# OneSideOfBoard.net
KiCad netlist of a schematic drawn in Altium Designer
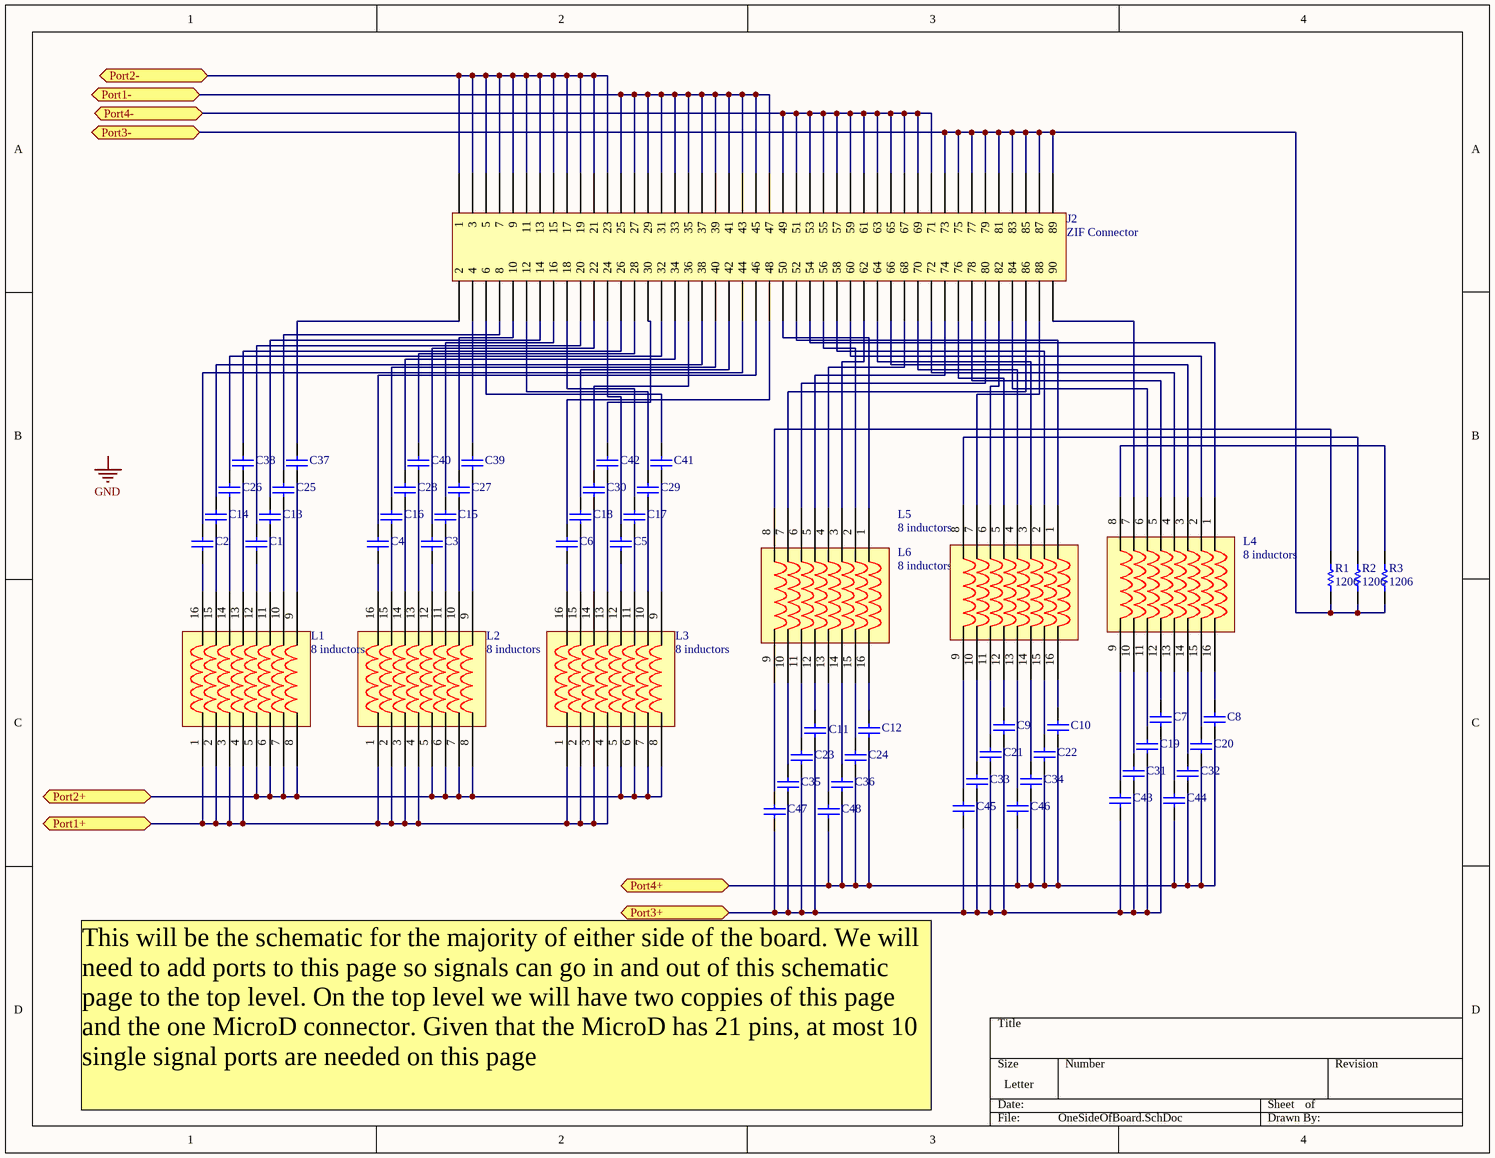
[diagram p0: OneSideOfBoard.SchDoc]

(export (version "E")
  (design (tool "Eeschema 10.0.6"))
  (components
    (comp (ref "C1")
      (value "47nF")
      (footprint "CC3216-1206")
      (description "Capacitor (Semiconductor SIM Model)")
      (fields (field (name "PUBLISHER") "Altium Limited"))
      (libsource (lib "altium-import") (part "root_1_Cap Semi_1_"))
    )
    (comp (ref "C2")
      (value "47nF")
      (footprint "CC3216-1206")
      (description "Capacitor (Semiconductor SIM Model)")
      (fields (field (name "PUBLISHER") "Altium Limited"))
      (libsource (lib "altium-import") (part "root_1_Cap Semi_1_"))
    )
    (comp (ref "C3")
      (value "47nF")
      (footprint "CC3216-1206")
      (description "Capacitor (Semiconductor SIM Model)")
      (fields (field (name "PUBLISHER") "Altium Limited"))
      (libsource (lib "altium-import") (part "root_1_Cap Semi_1_"))
    )
    (comp (ref "C4")
      (value "47nF")
      (footprint "CC3216-1206")
      (description "Capacitor (Semiconductor SIM Model)")
      (fields (field (name "PUBLISHER") "Altium Limited"))
      (libsource (lib "altium-import") (part "root_1_Cap Semi_1_"))
    )
    (comp (ref "C5")
      (value "47nF")
      (footprint "CC3216-1206")
      (description "Capacitor (Semiconductor SIM Model)")
      (fields (field (name "PUBLISHER") "Altium Limited"))
      (libsource (lib "altium-import") (part "root_1_Cap Semi_1_"))
    )
    (comp (ref "C6")
      (value "47nF")
      (footprint "CC3216-1206")
      (description "Capacitor (Semiconductor SIM Model)")
      (fields (field (name "PUBLISHER") "Altium Limited"))
      (libsource (lib "altium-import") (part "root_1_Cap Semi_1_"))
    )
    (comp (ref "C7")
      (value "47nF")
      (footprint "CC3216-1206")
      (description "Capacitor (Semiconductor SIM Model)")
      (fields (field (name "PUBLISHER") "Altium Limited"))
      (libsource (lib "altium-import") (part "root_3_Cap Semi_1_"))
    )
    (comp (ref "C8")
      (value "47nF")
      (footprint "CC3216-1206")
      (description "Capacitor (Semiconductor SIM Model)")
      (fields (field (name "PUBLISHER") "Altium Limited"))
      (libsource (lib "altium-import") (part "root_3_Cap Semi_1_"))
    )
    (comp (ref "C9")
      (value "47nF")
      (footprint "CC3216-1206")
      (description "Capacitor (Semiconductor SIM Model)")
      (fields (field (name "PUBLISHER") "Altium Limited"))
      (libsource (lib "altium-import") (part "root_3_Cap Semi_1_"))
    )
    (comp (ref "C10")
      (value "47nF")
      (footprint "CC3216-1206")
      (description "Capacitor (Semiconductor SIM Model)")
      (fields (field (name "PUBLISHER") "Altium Limited"))
      (libsource (lib "altium-import") (part "root_3_Cap Semi_1_"))
    )
    (comp (ref "C11")
      (value "47nF")
      (footprint "CC3216-1206")
      (description "Capacitor (Semiconductor SIM Model)")
      (fields (field (name "PUBLISHER") "Altium Limited"))
      (libsource (lib "altium-import") (part "root_3_Cap Semi_1_"))
    )
    (comp (ref "C12")
      (value "47nF")
      (footprint "CC3216-1206")
      (description "Capacitor (Semiconductor SIM Model)")
      (fields (field (name "PUBLISHER") "Altium Limited"))
      (libsource (lib "altium-import") (part "root_3_Cap Semi_1_"))
    )
    (comp (ref "C13")
      (value "47nF")
      (footprint "CC3216-1206")
      (description "Capacitor (Semiconductor SIM Model)")
      (fields (field (name "PUBLISHER") "Altium Limited"))
      (libsource (lib "altium-import") (part "root_1_Cap Semi_1_"))
    )
    (comp (ref "C14")
      (value "47nF")
      (footprint "CC3216-1206")
      (description "Capacitor (Semiconductor SIM Model)")
      (fields (field (name "PUBLISHER") "Altium Limited"))
      (libsource (lib "altium-import") (part "root_1_Cap Semi_1_"))
    )
    (comp (ref "C15")
      (value "47nF")
      (footprint "CC3216-1206")
      (description "Capacitor (Semiconductor SIM Model)")
      (fields (field (name "PUBLISHER") "Altium Limited"))
      (libsource (lib "altium-import") (part "root_1_Cap Semi_1_"))
    )
    (comp (ref "C16")
      (value "47nF")
      (footprint "CC3216-1206")
      (description "Capacitor (Semiconductor SIM Model)")
      (fields (field (name "PUBLISHER") "Altium Limited"))
      (libsource (lib "altium-import") (part "root_1_Cap Semi_1_"))
    )
    (comp (ref "C17")
      (value "47nF")
      (footprint "CC3216-1206")
      (description "Capacitor (Semiconductor SIM Model)")
      (fields (field (name "PUBLISHER") "Altium Limited"))
      (libsource (lib "altium-import") (part "root_1_Cap Semi_1_"))
    )
    (comp (ref "C18")
      (value "47nF")
      (footprint "CC3216-1206")
      (description "Capacitor (Semiconductor SIM Model)")
      (fields (field (name "PUBLISHER") "Altium Limited"))
      (libsource (lib "altium-import") (part "root_1_Cap Semi_1_"))
    )
    (comp (ref "C19")
      (value "47nF")
      (footprint "CC3216-1206")
      (description "Capacitor (Semiconductor SIM Model)")
      (fields (field (name "PUBLISHER") "Altium Limited"))
      (libsource (lib "altium-import") (part "root_3_Cap Semi_1_"))
    )
    (comp (ref "C20")
      (value "47nF")
      (footprint "CC3216-1206")
      (description "Capacitor (Semiconductor SIM Model)")
      (fields (field (name "PUBLISHER") "Altium Limited"))
      (libsource (lib "altium-import") (part "root_3_Cap Semi_1_"))
    )
    (comp (ref "C21")
      (value "47nF")
      (footprint "CC3216-1206")
      (description "Capacitor (Semiconductor SIM Model)")
      (fields (field (name "PUBLISHER") "Altium Limited"))
      (libsource (lib "altium-import") (part "root_3_Cap Semi_1_"))
    )
    (comp (ref "C22")
      (value "47nF")
      (footprint "CC3216-1206")
      (description "Capacitor (Semiconductor SIM Model)")
      (fields (field (name "PUBLISHER") "Altium Limited"))
      (libsource (lib "altium-import") (part "root_3_Cap Semi_1_"))
    )
    (comp (ref "C23")
      (value "47nF")
      (footprint "CC3216-1206")
      (description "Capacitor (Semiconductor SIM Model)")
      (fields (field (name "PUBLISHER") "Altium Limited"))
      (libsource (lib "altium-import") (part "root_3_Cap Semi_1_"))
    )
    (comp (ref "C24")
      (value "47nF")
      (footprint "CC3216-1206")
      (description "Capacitor (Semiconductor SIM Model)")
      (fields (field (name "PUBLISHER") "Altium Limited"))
      (libsource (lib "altium-import") (part "root_3_Cap Semi_1_"))
    )
    (comp (ref "C25")
      (value "47nF")
      (footprint "CC3216-1206")
      (description "Capacitor (Semiconductor SIM Model)")
      (fields (field (name "PUBLISHER") "Altium Limited"))
      (libsource (lib "altium-import") (part "root_1_Cap Semi_1_"))
    )
    (comp (ref "C26")
      (value "47nF")
      (footprint "CC3216-1206")
      (description "Capacitor (Semiconductor SIM Model)")
      (fields (field (name "PUBLISHER") "Altium Limited"))
      (libsource (lib "altium-import") (part "root_1_Cap Semi_1_"))
    )
    (comp (ref "C27")
      (value "47nF")
      (footprint "CC3216-1206")
      (description "Capacitor (Semiconductor SIM Model)")
      (fields (field (name "PUBLISHER") "Altium Limited"))
      (libsource (lib "altium-import") (part "root_1_Cap Semi_1_"))
    )
    (comp (ref "C28")
      (value "47nF")
      (footprint "CC3216-1206")
      (description "Capacitor (Semiconductor SIM Model)")
      (fields (field (name "PUBLISHER") "Altium Limited"))
      (libsource (lib "altium-import") (part "root_1_Cap Semi_1_"))
    )
    (comp (ref "C29")
      (value "47nF")
      (footprint "CC3216-1206")
      (description "Capacitor (Semiconductor SIM Model)")
      (fields (field (name "PUBLISHER") "Altium Limited"))
      (libsource (lib "altium-import") (part "root_1_Cap Semi_1_"))
    )
    (comp (ref "C30")
      (value "47nF")
      (footprint "CC3216-1206")
      (description "Capacitor (Semiconductor SIM Model)")
      (fields (field (name "PUBLISHER") "Altium Limited"))
      (libsource (lib "altium-import") (part "root_1_Cap Semi_1_"))
    )
    (comp (ref "C31")
      (value "47nF")
      (footprint "CC3216-1206")
      (description "Capacitor (Semiconductor SIM Model)")
      (fields (field (name "PUBLISHER") "Altium Limited"))
      (libsource (lib "altium-import") (part "root_3_Cap Semi_1_"))
    )
    (comp (ref "C32")
      (value "47nF")
      (footprint "CC3216-1206")
      (description "Capacitor (Semiconductor SIM Model)")
      (fields (field (name "PUBLISHER") "Altium Limited"))
      (libsource (lib "altium-import") (part "root_3_Cap Semi_1_"))
    )
    (comp (ref "C33")
      (value "47nF")
      (footprint "CC3216-1206")
      (description "Capacitor (Semiconductor SIM Model)")
      (fields (field (name "PUBLISHER") "Altium Limited"))
      (libsource (lib "altium-import") (part "root_3_Cap Semi_1_"))
    )
    (comp (ref "C34")
      (value "47nF")
      (footprint "CC3216-1206")
      (description "Capacitor (Semiconductor SIM Model)")
      (fields (field (name "PUBLISHER") "Altium Limited"))
      (libsource (lib "altium-import") (part "root_3_Cap Semi_1_"))
    )
    (comp (ref "C35")
      (value "47nF")
      (footprint "CC3216-1206")
      (description "Capacitor (Semiconductor SIM Model)")
      (fields (field (name "PUBLISHER") "Altium Limited"))
      (libsource (lib "altium-import") (part "root_3_Cap Semi_1_"))
    )
    (comp (ref "C36")
      (value "47nF")
      (footprint "CC3216-1206")
      (description "Capacitor (Semiconductor SIM Model)")
      (fields (field (name "PUBLISHER") "Altium Limited"))
      (libsource (lib "altium-import") (part "root_3_Cap Semi_1_"))
    )
    (comp (ref "C37")
      (value "47nF")
      (footprint "CC3216-1206")
      (description "Capacitor (Semiconductor SIM Model)")
      (fields (field (name "PUBLISHER") "Altium Limited"))
      (libsource (lib "altium-import") (part "root_1_Cap Semi_1_"))
    )
    (comp (ref "C38")
      (value "47nF")
      (footprint "CC3216-1206")
      (description "Capacitor (Semiconductor SIM Model)")
      (fields (field (name "PUBLISHER") "Altium Limited"))
      (libsource (lib "altium-import") (part "root_1_Cap Semi_1_"))
    )
    (comp (ref "C39")
      (value "47nF")
      (footprint "CC3216-1206")
      (description "Capacitor (Semiconductor SIM Model)")
      (fields (field (name "PUBLISHER") "Altium Limited"))
      (libsource (lib "altium-import") (part "root_1_Cap Semi_1_"))
    )
    (comp (ref "C40")
      (value "47nF")
      (footprint "CC3216-1206")
      (description "Capacitor (Semiconductor SIM Model)")
      (fields (field (name "PUBLISHER") "Altium Limited"))
      (libsource (lib "altium-import") (part "root_1_Cap Semi_1_"))
    )
    (comp (ref "C41")
      (value "47nF")
      (footprint "CC3216-1206")
      (description "Capacitor (Semiconductor SIM Model)")
      (fields (field (name "PUBLISHER") "Altium Limited"))
      (libsource (lib "altium-import") (part "root_1_Cap Semi_1_"))
    )
    (comp (ref "C42")
      (value "47nF")
      (footprint "CC3216-1206")
      (description "Capacitor (Semiconductor SIM Model)")
      (fields (field (name "PUBLISHER") "Altium Limited"))
      (libsource (lib "altium-import") (part "root_1_Cap Semi_1_"))
    )
    (comp (ref "C43")
      (value "47nF")
      (footprint "CC3216-1206")
      (description "Capacitor (Semiconductor SIM Model)")
      (fields (field (name "PUBLISHER") "Altium Limited"))
      (libsource (lib "altium-import") (part "root_3_Cap Semi_1_"))
    )
    (comp (ref "C44")
      (value "47nF")
      (footprint "CC3216-1206")
      (description "Capacitor (Semiconductor SIM Model)")
      (fields (field (name "PUBLISHER") "Altium Limited"))
      (libsource (lib "altium-import") (part "root_3_Cap Semi_1_"))
    )
    (comp (ref "C45")
      (value "47nF")
      (footprint "CC3216-1206")
      (description "Capacitor (Semiconductor SIM Model)")
      (fields (field (name "PUBLISHER") "Altium Limited"))
      (libsource (lib "altium-import") (part "root_3_Cap Semi_1_"))
    )
    (comp (ref "C46")
      (value "47nF")
      (footprint "CC3216-1206")
      (description "Capacitor (Semiconductor SIM Model)")
      (fields (field (name "PUBLISHER") "Altium Limited"))
      (libsource (lib "altium-import") (part "root_3_Cap Semi_1_"))
    )
    (comp (ref "C47")
      (value "47nF")
      (footprint "CC3216-1206")
      (description "Capacitor (Semiconductor SIM Model)")
      (fields (field (name "PUBLISHER") "Altium Limited"))
      (libsource (lib "altium-import") (part "root_3_Cap Semi_1_"))
    )
    (comp (ref "C48")
      (value "47nF")
      (footprint "CC3216-1206")
      (description "Capacitor (Semiconductor SIM Model)")
      (fields (field (name "PUBLISHER") "Altium Limited"))
      (libsource (lib "altium-import") (part "root_3_Cap Semi_1_"))
    )
    (comp (ref "J2")
      (value "ZIF Connector")
      (footprint "LCBoard_ZIFCon")
      (libsource (lib "altium-import") (part "root_1_LCboard_FH16-90S-0.3SHW(05)_"))
    )
    (comp (ref "L1")
      (value "8 inductors")
      (footprint "LCboardInductor8")
      (libsource (lib "altium-import") (part "root_1_LCboardInductor8_"))
    )
    (comp (ref "L2")
      (value "8 inductors")
      (footprint "LCboardInductor8")
      (libsource (lib "altium-import") (part "root_1_LCboardInductor8_"))
    )
    (comp (ref "L3")
      (value "8 inductors")
      (footprint "LCboardInductor8")
      (libsource (lib "altium-import") (part "root_1_LCboardInductor8_"))
    )
    (comp (ref "L4")
      (value "8 inductors")
      (footprint "LCboardInductor8")
      (libsource (lib "altium-import") (part "root_3_LCboardInductor8_"))
    )
    (comp (ref "L5")
      (value "8 inductors")
      (footprint "LCboardInductor8")
      (libsource (lib "altium-import") (part "root_3_LCboardInductor8_"))
    )
    (comp (ref "L6")
      (value "8 inductors")
      (footprint "LCboardInductor8")
      (libsource (lib "altium-import") (part "root_3_LCboardInductor8_"))
    )
    (comp (ref "R1")
      (value "~")
      (footprint "1206")
      (description "Resistor")
      (libsource (lib "altium-import") (part "root_1_Res1206_"))
    )
    (comp (ref "R2")
      (value "~")
      (footprint "1206")
      (description "Resistor")
      (libsource (lib "altium-import") (part "root_1_Res1206_"))
    )
    (comp (ref "R3")
      (value "~")
      (footprint "1206")
      (description "Resistor")
      (libsource (lib "altium-import") (part "root_1_Res1206_"))
    )
  )
  (nets
    (net (code "1") (name "/Port1+") (class "Default")
      (node (ref "L1") (pin "1") (pinfunction "1_1") (pintype "passive"))
      (node (ref "L1") (pin "2") (pinfunction "2_2") (pintype "passive"))
      (node (ref "L1") (pin "3") (pinfunction "3_3") (pintype "passive"))
      (node (ref "L1") (pin "4") (pinfunction "4_4") (pintype "passive"))
      (node (ref "L2") (pin "1") (pinfunction "1_1") (pintype "passive"))
      (node (ref "L2") (pin "2") (pinfunction "2_2") (pintype "passive"))
      (node (ref "L2") (pin "3") (pinfunction "3_3") (pintype "passive"))
      (node (ref "L2") (pin "4") (pinfunction "4_4") (pintype "passive"))
      (node (ref "L3") (pin "1") (pinfunction "1_1") (pintype "passive"))
      (node (ref "L3") (pin "2") (pinfunction "2_2") (pintype "passive"))
      (node (ref "L3") (pin "3") (pinfunction "3_3") (pintype "passive"))
      (node (ref "L3") (pin "4") (pinfunction "4_4") (pintype "passive"))
    )
    (net (code "2") (name "/Port1-") (class "Default")
      (node (ref "J2") (pin "25") (pinfunction "25_25") (pintype "passive"))
      (node (ref "J2") (pin "27") (pinfunction "27_27") (pintype "passive"))
      (node (ref "J2") (pin "29") (pinfunction "29_29") (pintype "passive"))
      (node (ref "J2") (pin "31") (pinfunction "31_31") (pintype "passive"))
      (node (ref "J2") (pin "33") (pinfunction "33_33") (pintype "passive"))
      (node (ref "J2") (pin "35") (pinfunction "35_35") (pintype "passive"))
      (node (ref "J2") (pin "37") (pinfunction "37_37") (pintype "passive"))
      (node (ref "J2") (pin "39") (pinfunction "39_39") (pintype "passive"))
      (node (ref "J2") (pin "41") (pinfunction "41_41") (pintype "passive"))
      (node (ref "J2") (pin "43") (pinfunction "43_43") (pintype "passive"))
      (node (ref "J2") (pin "45") (pinfunction "45_45") (pintype "passive"))
      (node (ref "J2") (pin "47") (pinfunction "47_47") (pintype "passive"))
    )
    (net (code "3") (name "/Port2+") (class "Default")
      (node (ref "L1") (pin "5") (pinfunction "5_5") (pintype "passive"))
      (node (ref "L1") (pin "6") (pinfunction "6_6") (pintype "passive"))
      (node (ref "L1") (pin "7") (pinfunction "7_7") (pintype "passive"))
      (node (ref "L1") (pin "8") (pinfunction "8_8") (pintype "passive"))
      (node (ref "L2") (pin "5") (pinfunction "5_5") (pintype "passive"))
      (node (ref "L2") (pin "6") (pinfunction "6_6") (pintype "passive"))
      (node (ref "L2") (pin "7") (pinfunction "7_7") (pintype "passive"))
      (node (ref "L2") (pin "8") (pinfunction "8_8") (pintype "passive"))
      (node (ref "L3") (pin "5") (pinfunction "5_5") (pintype "passive"))
      (node (ref "L3") (pin "6") (pinfunction "6_6") (pintype "passive"))
      (node (ref "L3") (pin "7") (pinfunction "7_7") (pintype "passive"))
      (node (ref "L3") (pin "8") (pinfunction "8_8") (pintype "passive"))
    )
    (net (code "4") (name "/Port2-") (class "Default")
      (node (ref "J2") (pin "1") (pinfunction "1_1") (pintype "passive"))
      (node (ref "J2") (pin "11") (pinfunction "11_11") (pintype "passive"))
      (node (ref "J2") (pin "13") (pinfunction "13_13") (pintype "passive"))
      (node (ref "J2") (pin "15") (pinfunction "15_15") (pintype "passive"))
      (node (ref "J2") (pin "17") (pinfunction "17_17") (pintype "passive"))
      (node (ref "J2") (pin "19") (pinfunction "19_19") (pintype "passive"))
      (node (ref "J2") (pin "21") (pinfunction "21_21") (pintype "passive"))
      (node (ref "J2") (pin "23") (pinfunction "23_23") (pintype "passive"))
      (node (ref "J2") (pin "3") (pinfunction "3_3") (pintype "passive"))
      (node (ref "J2") (pin "5") (pinfunction "5_5") (pintype "passive"))
      (node (ref "J2") (pin "7") (pinfunction "7_7") (pintype "passive"))
      (node (ref "J2") (pin "9") (pinfunction "9_9") (pintype "passive"))
    )
    (net (code "5") (name "/Port3+") (class "Default")
      (node (ref "C11") (pin "2") (pinfunction "2_2") (pintype "passive"))
      (node (ref "C19") (pin "2") (pinfunction "2_2") (pintype "passive"))
      (node (ref "C21") (pin "2") (pinfunction "2_2") (pintype "passive"))
      (node (ref "C23") (pin "2") (pinfunction "2_2") (pintype "passive"))
      (node (ref "C31") (pin "2") (pinfunction "2_2") (pintype "passive"))
      (node (ref "C33") (pin "2") (pinfunction "2_2") (pintype "passive"))
      (node (ref "C35") (pin "2") (pinfunction "2_2") (pintype "passive"))
      (node (ref "C43") (pin "2") (pinfunction "2_2") (pintype "passive"))
      (node (ref "C45") (pin "2") (pinfunction "2_2") (pintype "passive"))
      (node (ref "C47") (pin "2") (pinfunction "2_2") (pintype "passive"))
      (node (ref "C7") (pin "2") (pinfunction "2_2") (pintype "passive"))
      (node (ref "C9") (pin "2") (pinfunction "2_2") (pintype "passive"))
    )
    (net (code "6") (name "/Port3-") (class "Default")
      (node (ref "J2") (pin "73") (pinfunction "73_73") (pintype "passive"))
      (node (ref "J2") (pin "75") (pinfunction "75_75") (pintype "passive"))
      (node (ref "J2") (pin "77") (pinfunction "77_77") (pintype "passive"))
      (node (ref "J2") (pin "79") (pinfunction "79_79") (pintype "passive"))
      (node (ref "J2") (pin "81") (pinfunction "81_81") (pintype "passive"))
      (node (ref "J2") (pin "83") (pinfunction "83_83") (pintype "passive"))
      (node (ref "J2") (pin "85") (pinfunction "85_85") (pintype "passive"))
      (node (ref "J2") (pin "87") (pinfunction "87_87") (pintype "passive"))
      (node (ref "J2") (pin "89") (pinfunction "89_89") (pintype "passive"))
      (node (ref "R1") (pin "1") (pinfunction "1_1") (pintype "passive"))
      (node (ref "R2") (pin "1") (pinfunction "1_1") (pintype "passive"))
      (node (ref "R3") (pin "1") (pinfunction "1_1") (pintype "passive"))
    )
    (net (code "7") (name "/Port4+") (class "Default")
      (node (ref "C10") (pin "2") (pinfunction "2_2") (pintype "passive"))
      (node (ref "C12") (pin "2") (pinfunction "2_2") (pintype "passive"))
      (node (ref "C20") (pin "2") (pinfunction "2_2") (pintype "passive"))
      (node (ref "C22") (pin "2") (pinfunction "2_2") (pintype "passive"))
      (node (ref "C24") (pin "2") (pinfunction "2_2") (pintype "passive"))
      (node (ref "C32") (pin "2") (pinfunction "2_2") (pintype "passive"))
      (node (ref "C34") (pin "2") (pinfunction "2_2") (pintype "passive"))
      (node (ref "C36") (pin "2") (pinfunction "2_2") (pintype "passive"))
      (node (ref "C44") (pin "2") (pinfunction "2_2") (pintype "passive"))
      (node (ref "C46") (pin "2") (pinfunction "2_2") (pintype "passive"))
      (node (ref "C48") (pin "2") (pinfunction "2_2") (pintype "passive"))
      (node (ref "C8") (pin "2") (pinfunction "2_2") (pintype "passive"))
    )
    (net (code "8") (name "/Port4-") (class "Default")
      (node (ref "J2") (pin "49") (pinfunction "49_49") (pintype "passive"))
      (node (ref "J2") (pin "51") (pinfunction "51_51") (pintype "passive"))
      (node (ref "J2") (pin "53") (pinfunction "53_53") (pintype "passive"))
      (node (ref "J2") (pin "55") (pinfunction "55_55") (pintype "passive"))
      (node (ref "J2") (pin "57") (pinfunction "57_57") (pintype "passive"))
      (node (ref "J2") (pin "59") (pinfunction "59_59") (pintype "passive"))
      (node (ref "J2") (pin "61") (pinfunction "61_61") (pintype "passive"))
      (node (ref "J2") (pin "63") (pinfunction "63_63") (pintype "passive"))
      (node (ref "J2") (pin "65") (pinfunction "65_65") (pintype "passive"))
      (node (ref "J2") (pin "67") (pinfunction "67_67") (pintype "passive"))
      (node (ref "J2") (pin "69") (pinfunction "69_69") (pintype "passive"))
      (node (ref "J2") (pin "71") (pinfunction "71_71") (pintype "passive"))
    )
    (net (code "10") (name "Net-(C1-Pad1)") (class "Default")
      (node (ref "C1") (pin "1") (pinfunction "1_1") (pintype "passive"))
      (node (ref "L1") (pin "12") (pinfunction "12_12") (pintype "passive"))
    )
    (net (code "11") (name "Net-(C1-Pad2)") (class "Default")
      (node (ref "C1") (pin "2") (pinfunction "2_2") (pintype "passive"))
      (node (ref "J2") (pin "20") (pinfunction "20_20") (pintype "passive"))
    )
    (net (code "12") (name "Net-(C2-Pad1)") (class "Default")
      (node (ref "C2") (pin "1") (pinfunction "1_1") (pintype "passive"))
      (node (ref "L1") (pin "16") (pinfunction "16_16") (pintype "passive"))
    )
    (net (code "13") (name "Net-(C2-Pad2)") (class "Default")
      (node (ref "C2") (pin "2") (pinfunction "2_2") (pintype "passive"))
      (node (ref "J2") (pin "44") (pinfunction "44_44") (pintype "passive"))
    )
    (net (code "14") (name "Net-(C3-Pad1)") (class "Default")
      (node (ref "C3") (pin "1") (pinfunction "1_1") (pintype "passive"))
      (node (ref "L2") (pin "12") (pinfunction "12_12") (pintype "passive"))
    )
    (net (code "15") (name "Net-(C3-Pad2)") (class "Default")
      (node (ref "C3") (pin "2") (pinfunction "2_2") (pintype "passive"))
      (node (ref "J2") (pin "22") (pinfunction "22_22") (pintype "passive"))
    )
    (net (code "16") (name "Net-(C4-Pad1)") (class "Default")
      (node (ref "C4") (pin "1") (pinfunction "1_1") (pintype "passive"))
      (node (ref "L2") (pin "16") (pinfunction "16_16") (pintype "passive"))
    )
    (net (code "17") (name "Net-(C4-Pad2)") (class "Default")
      (node (ref "C4") (pin "2") (pinfunction "2_2") (pintype "passive"))
      (node (ref "J2") (pin "46") (pinfunction "46_46") (pintype "passive"))
    )
    (net (code "18") (name "Net-(C5-Pad1)") (class "Default")
      (node (ref "C5") (pin "1") (pinfunction "1_1") (pintype "passive"))
      (node (ref "L3") (pin "12") (pinfunction "12_12") (pintype "passive"))
    )
    (net (code "19") (name "Net-(C5-Pad2)") (class "Default")
      (node (ref "C5") (pin "2") (pinfunction "2_2") (pintype "passive"))
      (node (ref "J2") (pin "24") (pinfunction "24_24") (pintype "passive"))
    )
    (net (code "20") (name "Net-(C6-Pad1)") (class "Default")
      (node (ref "C6") (pin "1") (pinfunction "1_1") (pintype "passive"))
      (node (ref "L3") (pin "16") (pinfunction "16_16") (pintype "passive"))
    )
    (net (code "21") (name "Net-(C6-Pad2)") (class "Default")
      (node (ref "C6") (pin "2") (pinfunction "2_2") (pintype "passive"))
      (node (ref "J2") (pin "48") (pinfunction "48_48") (pintype "passive"))
    )
    (net (code "22") (name "Net-(C7-Pad1)") (class "Default")
      (node (ref "C7") (pin "1") (pinfunction "1_1") (pintype "passive"))
      (node (ref "L4") (pin "12") (pinfunction "12_12") (pintype "passive"))
    )
    (net (code "23") (name "Net-(C8-Pad1)") (class "Default")
      (node (ref "C8") (pin "1") (pinfunction "1_1") (pintype "passive"))
      (node (ref "L4") (pin "16") (pinfunction "16_16") (pintype "passive"))
    )
    (net (code "24") (name "Net-(C9-Pad1)") (class "Default")
      (node (ref "C9") (pin "1") (pinfunction "1_1") (pintype "passive"))
      (node (ref "L5") (pin "12") (pinfunction "12_12") (pintype "passive"))
    )
    (net (code "25") (name "Net-(C10-Pad1)") (class "Default")
      (node (ref "C10") (pin "1") (pinfunction "1_1") (pintype "passive"))
      (node (ref "L5") (pin "16") (pinfunction "16_16") (pintype "passive"))
    )
    (net (code "26") (name "Net-(C11-Pad1)") (class "Default")
      (node (ref "C11") (pin "1") (pinfunction "1_1") (pintype "passive"))
      (node (ref "L6") (pin "12") (pinfunction "12_12") (pintype "passive"))
    )
    (net (code "27") (name "Net-(C12-Pad1)") (class "Default")
      (node (ref "C12") (pin "1") (pinfunction "1_1") (pintype "passive"))
      (node (ref "L6") (pin "16") (pinfunction "16_16") (pintype "passive"))
    )
    (net (code "28") (name "Net-(C13-Pad1)") (class "Default")
      (node (ref "C13") (pin "1") (pinfunction "1_1") (pintype "passive"))
      (node (ref "L1") (pin "11") (pinfunction "11_11") (pintype "passive"))
    )
    (net (code "29") (name "Net-(C13-Pad2)") (class "Default")
      (node (ref "C13") (pin "2") (pinfunction "2_2") (pintype "passive"))
      (node (ref "J2") (pin "14") (pinfunction "14_14") (pintype "passive"))
    )
    (net (code "30") (name "Net-(C14-Pad1)") (class "Default")
      (node (ref "C14") (pin "1") (pinfunction "1_1") (pintype "passive"))
      (node (ref "L1") (pin "15") (pinfunction "15_15") (pintype "passive"))
    )
    (net (code "31") (name "Net-(C14-Pad2)") (class "Default")
      (node (ref "C14") (pin "2") (pinfunction "2_2") (pintype "passive"))
      (node (ref "J2") (pin "38") (pinfunction "38_38") (pintype "passive"))
    )
    (net (code "32") (name "Net-(C15-Pad1)") (class "Default")
      (node (ref "C15") (pin "1") (pinfunction "1_1") (pintype "passive"))
      (node (ref "L2") (pin "11") (pinfunction "11_11") (pintype "passive"))
    )
    (net (code "33") (name "Net-(C15-Pad2)") (class "Default")
      (node (ref "C15") (pin "2") (pinfunction "2_2") (pintype "passive"))
      (node (ref "J2") (pin "16") (pinfunction "16_16") (pintype "passive"))
    )
    (net (code "34") (name "Net-(C16-Pad1)") (class "Default")
      (node (ref "C16") (pin "1") (pinfunction "1_1") (pintype "passive"))
      (node (ref "L2") (pin "15") (pinfunction "15_15") (pintype "passive"))
    )
    (net (code "35") (name "Net-(C16-Pad2)") (class "Default")
      (node (ref "C16") (pin "2") (pinfunction "2_2") (pintype "passive"))
      (node (ref "J2") (pin "40") (pinfunction "40_40") (pintype "passive"))
    )
    (net (code "36") (name "Net-(C17-Pad1)") (class "Default")
      (node (ref "C17") (pin "1") (pinfunction "1_1") (pintype "passive"))
      (node (ref "L3") (pin "11") (pinfunction "11_11") (pintype "passive"))
    )
    (net (code "37") (name "Net-(C17-Pad2)") (class "Default")
      (node (ref "C17") (pin "2") (pinfunction "2_2") (pintype "passive"))
      (node (ref "J2") (pin "18") (pinfunction "18_18") (pintype "passive"))
    )
    (net (code "38") (name "Net-(C18-Pad1)") (class "Default")
      (node (ref "C18") (pin "1") (pinfunction "1_1") (pintype "passive"))
      (node (ref "L3") (pin "15") (pinfunction "15_15") (pintype "passive"))
    )
    (net (code "39") (name "Net-(C18-Pad2)") (class "Default")
      (node (ref "C18") (pin "2") (pinfunction "2_2") (pintype "passive"))
      (node (ref "J2") (pin "42") (pinfunction "42_42") (pintype "passive"))
    )
    (net (code "40") (name "Net-(C19-Pad1)") (class "Default")
      (node (ref "C19") (pin "1") (pinfunction "1_1") (pintype "passive"))
      (node (ref "L4") (pin "11") (pinfunction "11_11") (pintype "passive"))
    )
    (net (code "41") (name "Net-(C20-Pad1)") (class "Default")
      (node (ref "C20") (pin "1") (pinfunction "1_1") (pintype "passive"))
      (node (ref "L4") (pin "15") (pinfunction "15_15") (pintype "passive"))
    )
    (net (code "42") (name "Net-(C21-Pad1)") (class "Default")
      (node (ref "C21") (pin "1") (pinfunction "1_1") (pintype "passive"))
      (node (ref "L5") (pin "11") (pinfunction "11_11") (pintype "passive"))
    )
    (net (code "43") (name "Net-(C22-Pad1)") (class "Default")
      (node (ref "C22") (pin "1") (pinfunction "1_1") (pintype "passive"))
      (node (ref "L5") (pin "15") (pinfunction "15_15") (pintype "passive"))
    )
    (net (code "44") (name "Net-(C23-Pad1)") (class "Default")
      (node (ref "C23") (pin "1") (pinfunction "1_1") (pintype "passive"))
      (node (ref "L6") (pin "11") (pinfunction "11_11") (pintype "passive"))
    )
    (net (code "45") (name "Net-(C24-Pad1)") (class "Default")
      (node (ref "C24") (pin "1") (pinfunction "1_1") (pintype "passive"))
      (node (ref "L6") (pin "15") (pinfunction "15_15") (pintype "passive"))
    )
    (net (code "46") (name "Net-(C25-Pad1)") (class "Default")
      (node (ref "C25") (pin "1") (pinfunction "1_1") (pintype "passive"))
      (node (ref "L1") (pin "10") (pinfunction "10_10") (pintype "passive"))
    )
    (net (code "47") (name "Net-(C25-Pad2)") (class "Default")
      (node (ref "C25") (pin "2") (pinfunction "2_2") (pintype "passive"))
      (node (ref "J2") (pin "8") (pinfunction "8_8") (pintype "passive"))
    )
    (net (code "48") (name "Net-(C26-Pad1)") (class "Default")
      (node (ref "C26") (pin "1") (pinfunction "1_1") (pintype "passive"))
      (node (ref "L1") (pin "14") (pinfunction "14_14") (pintype "passive"))
    )
    (net (code "49") (name "Net-(C26-Pad2)") (class "Default")
      (node (ref "C26") (pin "2") (pinfunction "2_2") (pintype "passive"))
      (node (ref "J2") (pin "32") (pinfunction "32_32") (pintype "passive"))
    )
    (net (code "50") (name "Net-(C27-Pad1)") (class "Default")
      (node (ref "C27") (pin "1") (pinfunction "1_1") (pintype "passive"))
      (node (ref "L2") (pin "10") (pinfunction "10_10") (pintype "passive"))
    )
    (net (code "51") (name "Net-(C27-Pad2)") (class "Default")
      (node (ref "C27") (pin "2") (pinfunction "2_2") (pintype "passive"))
      (node (ref "J2") (pin "10") (pinfunction "10_10") (pintype "passive"))
    )
    (net (code "52") (name "Net-(C28-Pad1)") (class "Default")
      (node (ref "C28") (pin "1") (pinfunction "1_1") (pintype "passive"))
      (node (ref "L2") (pin "14") (pinfunction "14_14") (pintype "passive"))
    )
    (net (code "53") (name "Net-(C28-Pad2)") (class "Default")
      (node (ref "C28") (pin "2") (pinfunction "2_2") (pintype "passive"))
      (node (ref "J2") (pin "34") (pinfunction "34_34") (pintype "passive"))
    )
    (net (code "54") (name "Net-(C29-Pad1)") (class "Default")
      (node (ref "C29") (pin "1") (pinfunction "1_1") (pintype "passive"))
      (node (ref "L3") (pin "10") (pinfunction "10_10") (pintype "passive"))
    )
    (net (code "55") (name "Net-(C29-Pad2)") (class "Default")
      (node (ref "C29") (pin "2") (pinfunction "2_2") (pintype "passive"))
      (node (ref "J2") (pin "12") (pinfunction "12_12") (pintype "passive"))
    )
    (net (code "56") (name "Net-(C30-Pad1)") (class "Default")
      (node (ref "C30") (pin "1") (pinfunction "1_1") (pintype "passive"))
      (node (ref "L3") (pin "14") (pinfunction "14_14") (pintype "passive"))
    )
    (net (code "57") (name "Net-(C30-Pad2)") (class "Default")
      (node (ref "C30") (pin "2") (pinfunction "2_2") (pintype "passive"))
      (node (ref "J2") (pin "36") (pinfunction "36_36") (pintype "passive"))
    )
    (net (code "58") (name "Net-(C31-Pad1)") (class "Default")
      (node (ref "C31") (pin "1") (pinfunction "1_1") (pintype "passive"))
      (node (ref "L4") (pin "10") (pinfunction "10_10") (pintype "passive"))
    )
    (net (code "59") (name "Net-(C32-Pad1)") (class "Default")
      (node (ref "C32") (pin "1") (pinfunction "1_1") (pintype "passive"))
      (node (ref "L4") (pin "14") (pinfunction "14_14") (pintype "passive"))
    )
    (net (code "60") (name "Net-(C33-Pad1)") (class "Default")
      (node (ref "C33") (pin "1") (pinfunction "1_1") (pintype "passive"))
      (node (ref "L5") (pin "10") (pinfunction "10_10") (pintype "passive"))
    )
    (net (code "61") (name "Net-(C34-Pad1)") (class "Default")
      (node (ref "C34") (pin "1") (pinfunction "1_1") (pintype "passive"))
      (node (ref "L5") (pin "14") (pinfunction "14_14") (pintype "passive"))
    )
    (net (code "62") (name "Net-(C35-Pad1)") (class "Default")
      (node (ref "C35") (pin "1") (pinfunction "1_1") (pintype "passive"))
      (node (ref "L6") (pin "10") (pinfunction "10_10") (pintype "passive"))
    )
    (net (code "63") (name "Net-(C36-Pad1)") (class "Default")
      (node (ref "C36") (pin "1") (pinfunction "1_1") (pintype "passive"))
      (node (ref "L6") (pin "14") (pinfunction "14_14") (pintype "passive"))
    )
    (net (code "64") (name "Net-(C37-Pad1)") (class "Default")
      (node (ref "C37") (pin "1") (pinfunction "1_1") (pintype "passive"))
      (node (ref "L1") (pin "9") (pinfunction "9_9") (pintype "passive"))
    )
    (net (code "65") (name "Net-(C37-Pad2)") (class "Default")
      (node (ref "C37") (pin "2") (pinfunction "2_2") (pintype "passive"))
      (node (ref "J2") (pin "2") (pinfunction "2_2") (pintype "passive"))
    )
    (net (code "66") (name "Net-(C38-Pad1)") (class "Default")
      (node (ref "C38") (pin "1") (pinfunction "1_1") (pintype "passive"))
      (node (ref "L1") (pin "13") (pinfunction "13_13") (pintype "passive"))
    )
    (net (code "67") (name "Net-(C38-Pad2)") (class "Default")
      (node (ref "C38") (pin "2") (pinfunction "2_2") (pintype "passive"))
      (node (ref "J2") (pin "26") (pinfunction "26_26") (pintype "passive"))
    )
    (net (code "68") (name "Net-(C39-Pad1)") (class "Default")
      (node (ref "C39") (pin "1") (pinfunction "1_1") (pintype "passive"))
      (node (ref "L2") (pin "9") (pinfunction "9_9") (pintype "passive"))
    )
    (net (code "69") (name "Net-(C39-Pad2)") (class "Default")
      (node (ref "C39") (pin "2") (pinfunction "2_2") (pintype "passive"))
      (node (ref "J2") (pin "4") (pinfunction "4_4") (pintype "passive"))
    )
    (net (code "70") (name "Net-(C40-Pad1)") (class "Default")
      (node (ref "C40") (pin "1") (pinfunction "1_1") (pintype "passive"))
      (node (ref "L2") (pin "13") (pinfunction "13_13") (pintype "passive"))
    )
    (net (code "71") (name "Net-(C40-Pad2)") (class "Default")
      (node (ref "C40") (pin "2") (pinfunction "2_2") (pintype "passive"))
      (node (ref "J2") (pin "28") (pinfunction "28_28") (pintype "passive"))
    )
    (net (code "72") (name "Net-(C41-Pad1)") (class "Default")
      (node (ref "C41") (pin "1") (pinfunction "1_1") (pintype "passive"))
      (node (ref "L3") (pin "9") (pinfunction "9_9") (pintype "passive"))
    )
    (net (code "73") (name "Net-(C41-Pad2)") (class "Default")
      (node (ref "C41") (pin "2") (pinfunction "2_2") (pintype "passive"))
      (node (ref "J2") (pin "6") (pinfunction "6_6") (pintype "passive"))
    )
    (net (code "74") (name "Net-(C42-Pad1)") (class "Default")
      (node (ref "C42") (pin "1") (pinfunction "1_1") (pintype "passive"))
      (node (ref "L3") (pin "13") (pinfunction "13_13") (pintype "passive"))
    )
    (net (code "75") (name "Net-(C42-Pad2)") (class "Default")
      (node (ref "C42") (pin "2") (pinfunction "2_2") (pintype "passive"))
      (node (ref "J2") (pin "30") (pinfunction "30_30") (pintype "passive"))
    )
    (net (code "76") (name "Net-(C43-Pad1)") (class "Default")
      (node (ref "C43") (pin "1") (pinfunction "1_1") (pintype "passive"))
      (node (ref "L4") (pin "9") (pinfunction "9_9") (pintype "passive"))
    )
    (net (code "77") (name "Net-(C44-Pad1)") (class "Default")
      (node (ref "C44") (pin "1") (pinfunction "1_1") (pintype "passive"))
      (node (ref "L4") (pin "13") (pinfunction "13_13") (pintype "passive"))
    )
    (net (code "78") (name "Net-(C45-Pad1)") (class "Default")
      (node (ref "C45") (pin "1") (pinfunction "1_1") (pintype "passive"))
      (node (ref "L5") (pin "9") (pinfunction "9_9") (pintype "passive"))
    )
    (net (code "79") (name "Net-(C46-Pad1)") (class "Default")
      (node (ref "C46") (pin "1") (pinfunction "1_1") (pintype "passive"))
      (node (ref "L5") (pin "13") (pinfunction "13_13") (pintype "passive"))
    )
    (net (code "80") (name "Net-(C47-Pad1)") (class "Default")
      (node (ref "C47") (pin "1") (pinfunction "1_1") (pintype "passive"))
      (node (ref "L6") (pin "9") (pinfunction "9_9") (pintype "passive"))
    )
    (net (code "81") (name "Net-(C48-Pad1)") (class "Default")
      (node (ref "C48") (pin "1") (pinfunction "1_1") (pintype "passive"))
      (node (ref "L6") (pin "13") (pinfunction "13_13") (pintype "passive"))
    )
    (net (code "82") (name "Net-(J2-Pad50)") (class "Default")
      (node (ref "J2") (pin "50") (pinfunction "50_50") (pintype "passive"))
      (node (ref "L6") (pin "1") (pinfunction "1_1") (pintype "passive"))
    )
    (net (code "83") (name "Net-(J2-Pad52)") (class "Default")
      (node (ref "J2") (pin "52") (pinfunction "52_52") (pintype "passive"))
      (node (ref "L5") (pin "1") (pinfunction "1_1") (pintype "passive"))
    )
    (net (code "84") (name "Net-(J2-Pad54)") (class "Default")
      (node (ref "J2") (pin "54") (pinfunction "54_54") (pintype "passive"))
      (node (ref "L4") (pin "1") (pinfunction "1_1") (pintype "passive"))
    )
    (net (code "85") (name "Net-(J2-Pad56)") (class "Default")
      (node (ref "J2") (pin "56") (pinfunction "56_56") (pintype "passive"))
      (node (ref "L6") (pin "2") (pinfunction "2_2") (pintype "passive"))
    )
    (net (code "86") (name "Net-(J2-Pad58)") (class "Default")
      (node (ref "J2") (pin "58") (pinfunction "58_58") (pintype "passive"))
      (node (ref "L5") (pin "2") (pinfunction "2_2") (pintype "passive"))
    )
    (net (code "87") (name "Net-(J2-Pad60)") (class "Default")
      (node (ref "J2") (pin "60") (pinfunction "60_60") (pintype "passive"))
      (node (ref "L4") (pin "2") (pinfunction "2_2") (pintype "passive"))
    )
    (net (code "88") (name "Net-(J2-Pad62)") (class "Default")
      (node (ref "J2") (pin "62") (pinfunction "62_62") (pintype "passive"))
      (node (ref "L6") (pin "3") (pinfunction "3_3") (pintype "passive"))
    )
    (net (code "89") (name "Net-(J2-Pad64)") (class "Default")
      (node (ref "J2") (pin "64") (pinfunction "64_64") (pintype "passive"))
      (node (ref "L5") (pin "3") (pinfunction "3_3") (pintype "passive"))
    )
    (net (code "90") (name "Net-(J2-Pad66)") (class "Default")
      (node (ref "J2") (pin "66") (pinfunction "66_66") (pintype "passive"))
      (node (ref "L4") (pin "3") (pinfunction "3_3") (pintype "passive"))
    )
    (net (code "91") (name "Net-(J2-Pad68)") (class "Default")
      (node (ref "J2") (pin "68") (pinfunction "68_68") (pintype "passive"))
      (node (ref "L6") (pin "4") (pinfunction "4_4") (pintype "passive"))
    )
    (net (code "92") (name "Net-(J2-Pad70)") (class "Default")
      (node (ref "J2") (pin "70") (pinfunction "70_70") (pintype "passive"))
      (node (ref "L5") (pin "4") (pinfunction "4_4") (pintype "passive"))
    )
    (net (code "93") (name "Net-(J2-Pad72)") (class "Default")
      (node (ref "J2") (pin "72") (pinfunction "72_72") (pintype "passive"))
      (node (ref "L4") (pin "4") (pinfunction "4_4") (pintype "passive"))
    )
    (net (code "94") (name "Net-(J2-Pad74)") (class "Default")
      (node (ref "J2") (pin "74") (pinfunction "74_74") (pintype "passive"))
      (node (ref "L6") (pin "5") (pinfunction "5_5") (pintype "passive"))
    )
    (net (code "95") (name "Net-(J2-Pad76)") (class "Default")
      (node (ref "J2") (pin "76") (pinfunction "76_76") (pintype "passive"))
      (node (ref "L5") (pin "5") (pinfunction "5_5") (pintype "passive"))
    )
    (net (code "96") (name "Net-(J2-Pad78)") (class "Default")
      (node (ref "J2") (pin "78") (pinfunction "78_78") (pintype "passive"))
      (node (ref "L4") (pin "5") (pinfunction "5_5") (pintype "passive"))
    )
    (net (code "97") (name "Net-(J2-Pad80)") (class "Default")
      (node (ref "J2") (pin "80") (pinfunction "80_80") (pintype "passive"))
      (node (ref "L6") (pin "6") (pinfunction "6_6") (pintype "passive"))
    )
    (net (code "98") (name "Net-(J2-Pad82)") (class "Default")
      (node (ref "J2") (pin "82") (pinfunction "82_82") (pintype "passive"))
      (node (ref "L5") (pin "6") (pinfunction "6_6") (pintype "passive"))
    )
    (net (code "99") (name "Net-(J2-Pad84)") (class "Default")
      (node (ref "J2") (pin "84") (pinfunction "84_84") (pintype "passive"))
      (node (ref "L4") (pin "6") (pinfunction "6_6") (pintype "passive"))
    )
    (net (code "100") (name "Net-(J2-Pad86)") (class "Default")
      (node (ref "J2") (pin "86") (pinfunction "86_86") (pintype "passive"))
      (node (ref "L6") (pin "7") (pinfunction "7_7") (pintype "passive"))
    )
    (net (code "101") (name "Net-(J2-Pad88)") (class "Default")
      (node (ref "J2") (pin "88") (pinfunction "88_88") (pintype "passive"))
      (node (ref "L5") (pin "7") (pinfunction "7_7") (pintype "passive"))
    )
    (net (code "102") (name "Net-(J2-Pad90)") (class "Default")
      (node (ref "J2") (pin "90") (pinfunction "90_90") (pintype "passive"))
      (node (ref "L4") (pin "7") (pinfunction "7_7") (pintype "passive"))
    )
    (net (code "103") (name "Net-(L4-Pad8)") (class "Default")
      (node (ref "L4") (pin "8") (pinfunction "8_8") (pintype "passive"))
      (node (ref "R3") (pin "2") (pinfunction "2_2") (pintype "passive"))
    )
    (net (code "104") (name "Net-(L5-Pad8)") (class "Default")
      (node (ref "L5") (pin "8") (pinfunction "8_8") (pintype "passive"))
      (node (ref "R2") (pin "2") (pinfunction "2_2") (pintype "passive"))
    )
    (net (code "105") (name "Net-(L6-Pad8)") (class "Default")
      (node (ref "L6") (pin "8") (pinfunction "8_8") (pintype "passive"))
      (node (ref "R1") (pin "2") (pinfunction "2_2") (pintype "passive"))
    )
  )
)
